# cpuboard.net
KiCad netlist of a schematic drawn in EAGLE
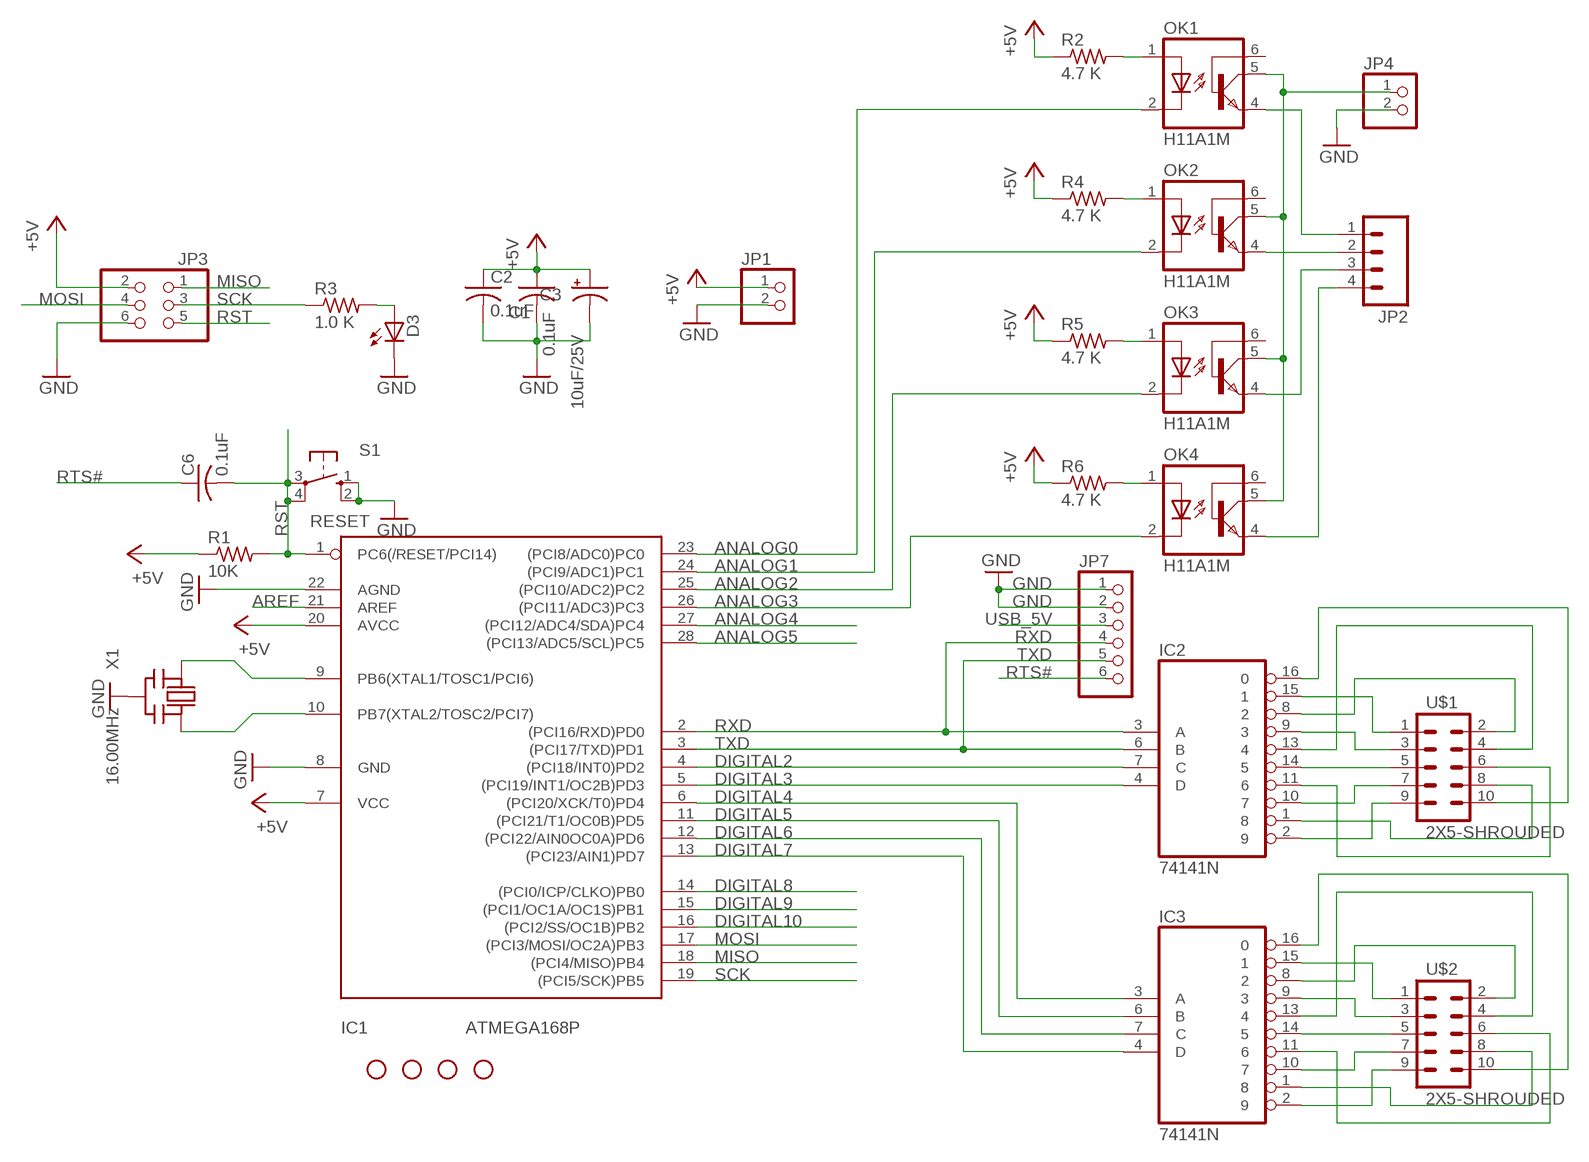
[diagram p0: schematic, sheet 1]

(export (version "E")
  (design (tool "Eeschema 10.0.6"))
  (components
    (comp (ref "C1")
      (value "0.1uF")
      (footprint "eagle-import:C025-025X050")
      (libsource (lib "eagle-import") (part "C-US025-025X050"))
    )
    (comp (ref "C2")
      (value "0.1uF")
      (footprint "eagle-import:C025-025X050")
      (libsource (lib "eagle-import") (part "C-US025-025X050"))
    )
    (comp (ref "C3")
      (value "10uF/25V")
      (footprint "eagle-import:E2,5-6")
      (libsource (lib "eagle-import") (part "CPOL-USE2.5-6"))
    )
    (comp (ref "C6")
      (value "0.1uF")
      (footprint "eagle-import:C025-025X050")
      (libsource (lib "eagle-import") (part "C-US025-025X050"))
    )
    (comp (ref "D3")
      (value "Green")
      (footprint "eagle-import:LED3MM")
      (libsource (lib "eagle-import") (part "LED3MM"))
    )
    (comp (ref "IC1")
      (value "ATMEGA168P")
      (footprint "eagle-import:DIL28_3")
      (libsource (lib "eagle-import") (part "ATMEGA168PROUND"))
    )
    (comp (ref "IC2")
      (value "74141N")
      (footprint "eagle-import:DIL16")
      (libsource (lib "eagle-import") (part "74141N"))
    )
    (comp (ref "IC3")
      (value "74141N")
      (footprint "eagle-import:DIL16")
      (libsource (lib "eagle-import") (part "74141N"))
    )
    (comp (ref "JP1")
      (value "PINHD-1X2CB")
      (footprint "eagle-import:1X02-CB")
      (libsource (lib "eagle-import") (part "PINHD-1X2CB"))
    )
    (comp (ref "JP2")
      (value "M04PTH")
      (footprint "eagle-import:1X04")
      (libsource (lib "eagle-import") (part "M04PTH"))
    )
    (comp (ref "JP3")
      (value "PINHD-2X3")
      (footprint "eagle-import:2X03")
      (libsource (lib "eagle-import") (part "PINHD-2X3"))
    )
    (comp (ref "JP4")
      (value "PINHD-1X2CB")
      (footprint "eagle-import:1X02-CB")
      (libsource (lib "eagle-import") (part "PINHD-1X2CB"))
    )
    (comp (ref "JP7")
      (value "PINHD-1X6CLEAN")
      (footprint "eagle-import:1X06-CLEAN")
      (libsource (lib "eagle-import") (part "PINHD-1X6CLEAN"))
    )
    (comp (ref "OK1")
      (value "H11A1M")
      (footprint "eagle-import:DIL06")
      (fields (field (name "MPN") "H11A1-M"))
      (libsource (lib "eagle-import") (part "H11A?M1"))
    )
    (comp (ref "OK2")
      (value "H11A1M")
      (footprint "eagle-import:DIL06")
      (fields (field (name "MPN") "H11A1-M"))
      (libsource (lib "eagle-import") (part "H11A?M1"))
    )
    (comp (ref "OK3")
      (value "H11A1M")
      (footprint "eagle-import:DIL06")
      (fields (field (name "MPN") "H11A1-M"))
      (libsource (lib "eagle-import") (part "H11A?M1"))
    )
    (comp (ref "OK4")
      (value "H11A1M")
      (footprint "eagle-import:DIL06")
      (fields (field (name "MPN") "H11A1-M"))
      (libsource (lib "eagle-import") (part "H11A?M1"))
    )
    (comp (ref "R1")
      (value "10K")
      (footprint "eagle-import:0207_5V")
      (libsource (lib "eagle-import") (part "rcl-ez_R-US_0207/5V"))
    )
    (comp (ref "R2")
      (value "4.7 K")
      (footprint "eagle-import:0207_5V")
      (libsource (lib "eagle-import") (part "R-US_0207/5V"))
    )
    (comp (ref "R3")
      (value "1.0 K")
      (footprint "eagle-import:0207_5V")
      (libsource (lib "eagle-import") (part "R-US_0207/5V"))
    )
    (comp (ref "R4")
      (value "4.7 K")
      (footprint "eagle-import:0207_5V")
      (libsource (lib "eagle-import") (part "R-US_0207/5V"))
    )
    (comp (ref "R5")
      (value "4.7 K")
      (footprint "eagle-import:0207_5V")
      (libsource (lib "eagle-import") (part "R-US_0207/5V"))
    )
    (comp (ref "R6")
      (value "4.7 K")
      (footprint "eagle-import:0207_5V")
      (libsource (lib "eagle-import") (part "R-US_0207/5V"))
    )
    (comp (ref "S1")
      (value "RESET")
      (footprint "eagle-import:B3F-10XX")
      (libsource (lib "eagle-import") (part "10-XX"))
    )
    (comp (ref "STANDOFF1")
      (value "STAND-OFF")
      (footprint "eagle-import:STAND-OFF")
      (libsource (lib "eagle-import") (part "STAND-OFF"))
    )
    (comp (ref "STANDOFF2")
      (value "STAND-OFF")
      (footprint "eagle-import:STAND-OFF")
      (libsource (lib "eagle-import") (part "STAND-OFF"))
    )
    (comp (ref "STANDOFF3")
      (value "STAND-OFF")
      (footprint "eagle-import:STAND-OFF")
      (libsource (lib "eagle-import") (part "STAND-OFF"))
    )
    (comp (ref "STANDOFF4")
      (value "STAND-OFF")
      (footprint "eagle-import:STAND-OFF")
      (libsource (lib "eagle-import") (part "STAND-OFF"))
    )
    (comp (ref "U$1")
      (value "2X5-SHROUDED")
      (footprint "eagle-import:2X5-SHROUDED")
      (libsource (lib "eagle-import") (part "2X5-SHROUDED"))
    )
    (comp (ref "U$2")
      (value "2X5-SHROUDED")
      (footprint "eagle-import:2X5-SHROUDED")
      (libsource (lib "eagle-import") (part "2X5-SHROUDED"))
    )
    (comp (ref "X1")
      (value "16.00MHz")
      (footprint "eagle-import:CERM_OSC")
      (libsource (lib "eagle-import") (part "CERMOSCILL"))
    )
  )
  (nets
    (net (code "1") (name "+5V") (class "Default")
      (node (ref "C1") (pin "1") (pinfunction "1_1") (pintype "passive"))
      (node (ref "C2") (pin "1") (pinfunction "1_1") (pintype "passive"))
      (node (ref "C3") (pin "+") (pinfunction "+_+") (pintype "passive"))
      (node (ref "IC1") (pin "20") (pinfunction "AVCC_20") (pintype "bidirectional"))
      (node (ref "IC1") (pin "7") (pinfunction "VCC_7") (pintype "bidirectional"))
      (node (ref "JP1") (pin "1") (pinfunction "1_1") (pintype "passive"))
      (node (ref "JP3") (pin "2") (pinfunction "2_2") (pintype "passive"))
      (node (ref "R1") (pin "1") (pinfunction "1_1") (pintype "passive"))
      (node (ref "R2") (pin "1") (pinfunction "1_1") (pintype "passive"))
      (node (ref "R4") (pin "1") (pinfunction "1_1") (pintype "passive"))
      (node (ref "R5") (pin "1") (pinfunction "1_1") (pintype "passive"))
      (node (ref "R6") (pin "1") (pinfunction "1_1") (pintype "passive"))
    )
    (net (code "2") (name "/ANALOG0") (class "Default")
      (node (ref "IC1") (pin "23") (pinfunction "(PCI8/ADC0)PC0_23") (pintype "bidirectional"))
      (node (ref "OK1") (pin "2") (pinfunction "C_2") (pintype "passive"))
    )
    (net (code "3") (name "/ANALOG1") (class "Default")
      (node (ref "IC1") (pin "24") (pinfunction "(PCI9/ADC1)PC1_24") (pintype "bidirectional"))
      (node (ref "OK2") (pin "2") (pinfunction "C_2") (pintype "passive"))
    )
    (net (code "4") (name "/ANALOG2") (class "Default")
      (node (ref "IC1") (pin "25") (pinfunction "(PCI10/ADC2)PC2_25") (pintype "bidirectional"))
      (node (ref "OK3") (pin "2") (pinfunction "C_2") (pintype "passive"))
    )
    (net (code "5") (name "/ANALOG3") (class "Default")
      (node (ref "IC1") (pin "26") (pinfunction "(PCI11/ADC3)PC3_26") (pintype "bidirectional"))
      (node (ref "OK4") (pin "2") (pinfunction "C_2") (pintype "passive"))
    )
    (net (code "6") (name "/ANALOG4") (class "Default")
      (node (ref "IC1") (pin "27") (pinfunction "(PCI12/ADC4/SDA)PC4_27") (pintype "bidirectional"))
    )
    (net (code "7") (name "/ANALOG5") (class "Default")
      (node (ref "IC1") (pin "28") (pinfunction "(PCI13/ADC5/SCL)PC5_28") (pintype "bidirectional"))
    )
    (net (code "8") (name "/AREF") (class "Default")
      (node (ref "IC1") (pin "21") (pinfunction "AREF_21") (pintype "bidirectional"))
    )
    (net (code "9") (name "/DIGITAL2") (class "Default")
      (node (ref "IC1") (pin "4") (pinfunction "(PCI18/INT0)PD2_4") (pintype "bidirectional"))
      (node (ref "IC2") (pin "7") (pinfunction "C_7") (pintype "input"))
    )
    (net (code "10") (name "/DIGITAL3") (class "Default")
      (node (ref "IC1") (pin "5") (pinfunction "(PCI19/INT1/OC2B)PD3_5") (pintype "bidirectional"))
      (node (ref "IC2") (pin "4") (pinfunction "D_4") (pintype "input"))
    )
    (net (code "11") (name "/DIGITAL4") (class "Default")
      (node (ref "IC1") (pin "6") (pinfunction "(PCI20/XCK/T0)PD4_6") (pintype "bidirectional"))
      (node (ref "IC3") (pin "3") (pinfunction "A_3") (pintype "input"))
    )
    (net (code "12") (name "/DIGITAL5") (class "Default")
      (node (ref "IC1") (pin "11") (pinfunction "(PCI21/T1/OC0B)PD5_11") (pintype "bidirectional"))
      (node (ref "IC3") (pin "6") (pinfunction "B_6") (pintype "input"))
    )
    (net (code "13") (name "/DIGITAL6") (class "Default")
      (node (ref "IC1") (pin "12") (pinfunction "(PCI22/AIN0OC0A)PD6_12") (pintype "bidirectional"))
      (node (ref "IC3") (pin "7") (pinfunction "C_7") (pintype "input"))
    )
    (net (code "14") (name "/DIGITAL7") (class "Default")
      (node (ref "IC1") (pin "13") (pinfunction "(PCI23/AIN1)PD7_13") (pintype "bidirectional"))
      (node (ref "IC3") (pin "4") (pinfunction "D_4") (pintype "input"))
    )
    (net (code "15") (name "/DIGITAL8") (class "Default")
      (node (ref "IC1") (pin "14") (pinfunction "(PCI0/ICP/CLKO)PB0_14") (pintype "bidirectional"))
    )
    (net (code "16") (name "/DIGITAL9") (class "Default")
      (node (ref "IC1") (pin "15") (pinfunction "(PCI1/OC1A/OC1S)PB1_15") (pintype "bidirectional"))
    )
    (net (code "17") (name "/DIGITAL10") (class "Default")
      (node (ref "IC1") (pin "16") (pinfunction "(PCI2/SS/OC1B)PB2_16") (pintype "bidirectional"))
    )
    (net (code "18") (name "/MISO") (class "Default")
      (node (ref "IC1") (pin "18") (pinfunction "(PCI4/MISO)PB4_18") (pintype "bidirectional"))
      (node (ref "JP3") (pin "1") (pinfunction "1_1") (pintype "passive"))
    )
    (net (code "19") (name "/MOSI") (class "Default")
      (node (ref "IC1") (pin "17") (pinfunction "(PCI3/MOSI/OC2A)PB3_17") (pintype "bidirectional"))
      (node (ref "JP3") (pin "4") (pinfunction "4_4") (pintype "passive"))
    )
    (net (code "20") (name "/RST") (class "Default")
      (node (ref "C6") (pin "2") (pinfunction "2_2") (pintype "passive"))
      (node (ref "IC1") (pin "1") (pinfunction "PC6(/RESET/PCI14)_1") (pintype "bidirectional"))
      (node (ref "JP3") (pin "5") (pinfunction "5_5") (pintype "passive"))
      (node (ref "R1") (pin "2") (pinfunction "2_2") (pintype "passive"))
      (node (ref "S1") (pin "3") (pinfunction "P_3") (pintype "passive"))
      (node (ref "S1") (pin "4") (pinfunction "P1_4") (pintype "passive"))
    )
    (net (code "21") (name "/RTS#") (class "Default")
      (node (ref "C6") (pin "1") (pinfunction "1_1") (pintype "passive"))
      (node (ref "JP7") (pin "6") (pinfunction "6_6") (pintype "passive"))
    )
    (net (code "22") (name "/RXD") (class "Default")
      (node (ref "IC1") (pin "2") (pinfunction "(PCI16/RXD)PD0_2") (pintype "bidirectional"))
      (node (ref "IC2") (pin "3") (pinfunction "A_3") (pintype "input"))
      (node (ref "JP7") (pin "4") (pinfunction "4_4") (pintype "passive"))
    )
    (net (code "23") (name "/SCK") (class "Default")
      (node (ref "IC1") (pin "19") (pinfunction "(PCI5/SCK)PB5_19") (pintype "bidirectional"))
      (node (ref "JP3") (pin "3") (pinfunction "3_3") (pintype "passive"))
      (node (ref "R3") (pin "1") (pinfunction "1_1") (pintype "passive"))
    )
    (net (code "24") (name "/TXD") (class "Default")
      (node (ref "IC1") (pin "3") (pinfunction "(PCI17/TXD)PD1_3") (pintype "bidirectional"))
      (node (ref "IC2") (pin "6") (pinfunction "B_6") (pintype "input"))
      (node (ref "JP7") (pin "5") (pinfunction "5_5") (pintype "passive"))
    )
    (net (code "25") (name "/USB_5V") (class "Default")
      (node (ref "JP7") (pin "3") (pinfunction "3_3") (pintype "passive"))
    )
    (net (code "26") (name "GND") (class "Default")
      (node (ref "C1") (pin "2") (pinfunction "2_2") (pintype "passive"))
      (node (ref "C2") (pin "2") (pinfunction "2_2") (pintype "passive"))
      (node (ref "C3") (pin "-") (pinfunction "-_-") (pintype "passive"))
      (node (ref "D3") (pin "K") (pinfunction "C_K") (pintype "passive"))
      (node (ref "IC1") (pin "22") (pinfunction "AGND_22") (pintype "bidirectional"))
      (node (ref "IC1") (pin "8") (pinfunction "GND_8") (pintype "bidirectional"))
      (node (ref "JP1") (pin "2") (pinfunction "2_2") (pintype "passive"))
      (node (ref "JP3") (pin "6") (pinfunction "6_6") (pintype "passive"))
      (node (ref "JP4") (pin "2") (pinfunction "2_2") (pintype "passive"))
      (node (ref "JP7") (pin "1") (pinfunction "1_1") (pintype "passive"))
      (node (ref "JP7") (pin "2") (pinfunction "2_2") (pintype "passive"))
      (node (ref "S1") (pin "1") (pinfunction "S_1") (pintype "passive"))
      (node (ref "S1") (pin "2") (pinfunction "S1_2") (pintype "passive"))
      (node (ref "X1") (pin "P$2") (pinfunction "GND_P$2") (pintype "bidirectional"))
    )
    (net (code "27") (name "Net-(D3-PadA)") (class "Default")
      (node (ref "D3") (pin "A") (pinfunction "A_A") (pintype "passive"))
      (node (ref "R3") (pin "2") (pinfunction "2_2") (pintype "passive"))
    )
    (net (code "28") (name "Net-(IC1-PB6(XTAL1{slash}TOSC1{slash}PCI6))") (class "Default")
      (node (ref "IC1") (pin "9") (pinfunction "PB6(XTAL1/TOSC1/PCI6)_9") (pintype "bidirectional"))
      (node (ref "X1") (pin "P$1") (pinfunction "IN_P$1") (pintype "bidirectional"))
    )
    (net (code "29") (name "Net-(IC1-PB7(XTAL2{slash}TOSC2{slash}PCI7))") (class "Default")
      (node (ref "IC1") (pin "10") (pinfunction "PB7(XTAL2/TOSC2/PCI7)_10") (pintype "bidirectional"))
      (node (ref "X1") (pin "P$3") (pinfunction "OUT_P$3") (pintype "bidirectional"))
    )
    (net (code "30") (name "Net-(IC2A-0)") (class "Default")
      (node (ref "IC2") (pin "16") (pinfunction "0_16") (pintype "open_collector"))
      (node (ref "U$1") (pin "10") (pinfunction "10_10") (pintype "passive"))
    )
    (net (code "31") (name "Net-(IC2A-1)") (class "Default")
      (node (ref "IC2") (pin "15") (pinfunction "1_15") (pintype "open_collector"))
      (node (ref "U$1") (pin "1") (pinfunction "1_1") (pintype "passive"))
    )
    (net (code "32") (name "Net-(IC2A-2)") (class "Default")
      (node (ref "IC2") (pin "8") (pinfunction "2_8") (pintype "open_collector"))
      (node (ref "U$1") (pin "2") (pinfunction "2_2") (pintype "passive"))
    )
    (net (code "33") (name "Net-(IC2A-3)") (class "Default")
      (node (ref "IC2") (pin "9") (pinfunction "3_9") (pintype "open_collector"))
      (node (ref "U$1") (pin "3") (pinfunction "3_3") (pintype "passive"))
    )
    (net (code "34") (name "Net-(IC2A-4)") (class "Default")
      (node (ref "IC2") (pin "13") (pinfunction "4_13") (pintype "open_collector"))
      (node (ref "U$1") (pin "4") (pinfunction "4_4") (pintype "passive"))
    )
    (net (code "35") (name "Net-(IC2A-5)") (class "Default")
      (node (ref "IC2") (pin "14") (pinfunction "5_14") (pintype "open_collector"))
      (node (ref "U$1") (pin "5") (pinfunction "5_5") (pintype "passive"))
    )
    (net (code "36") (name "Net-(IC2A-6)") (class "Default")
      (node (ref "IC2") (pin "11") (pinfunction "6_11") (pintype "open_collector"))
      (node (ref "U$1") (pin "6") (pinfunction "6_6") (pintype "passive"))
    )
    (net (code "37") (name "Net-(IC2A-7)") (class "Default")
      (node (ref "IC2") (pin "10") (pinfunction "7_10") (pintype "open_collector"))
      (node (ref "U$1") (pin "7") (pinfunction "7_7") (pintype "passive"))
    )
    (net (code "38") (name "Net-(IC2A-8)") (class "Default")
      (node (ref "IC2") (pin "1") (pinfunction "8_1") (pintype "open_collector"))
      (node (ref "U$1") (pin "8") (pinfunction "8_8") (pintype "passive"))
    )
    (net (code "39") (name "Net-(IC2A-9)") (class "Default")
      (node (ref "IC2") (pin "2") (pinfunction "9_2") (pintype "open_collector"))
      (node (ref "U$1") (pin "9") (pinfunction "9_9") (pintype "passive"))
    )
    (net (code "40") (name "Net-(IC3A-0)") (class "Default")
      (node (ref "IC3") (pin "16") (pinfunction "0_16") (pintype "open_collector"))
      (node (ref "U$2") (pin "10") (pinfunction "10_10") (pintype "passive"))
    )
    (net (code "41") (name "Net-(IC3A-1)") (class "Default")
      (node (ref "IC3") (pin "15") (pinfunction "1_15") (pintype "open_collector"))
      (node (ref "U$2") (pin "1") (pinfunction "1_1") (pintype "passive"))
    )
    (net (code "42") (name "Net-(IC3A-2)") (class "Default")
      (node (ref "IC3") (pin "8") (pinfunction "2_8") (pintype "open_collector"))
      (node (ref "U$2") (pin "2") (pinfunction "2_2") (pintype "passive"))
    )
    (net (code "43") (name "Net-(IC3A-3)") (class "Default")
      (node (ref "IC3") (pin "9") (pinfunction "3_9") (pintype "open_collector"))
      (node (ref "U$2") (pin "3") (pinfunction "3_3") (pintype "passive"))
    )
    (net (code "44") (name "Net-(IC3A-4)") (class "Default")
      (node (ref "IC3") (pin "13") (pinfunction "4_13") (pintype "open_collector"))
      (node (ref "U$2") (pin "4") (pinfunction "4_4") (pintype "passive"))
    )
    (net (code "45") (name "Net-(IC3A-5)") (class "Default")
      (node (ref "IC3") (pin "14") (pinfunction "5_14") (pintype "open_collector"))
      (node (ref "U$2") (pin "5") (pinfunction "5_5") (pintype "passive"))
    )
    (net (code "46") (name "Net-(IC3A-6)") (class "Default")
      (node (ref "IC3") (pin "11") (pinfunction "6_11") (pintype "open_collector"))
      (node (ref "U$2") (pin "6") (pinfunction "6_6") (pintype "passive"))
    )
    (net (code "47") (name "Net-(IC3A-7)") (class "Default")
      (node (ref "IC3") (pin "10") (pinfunction "7_10") (pintype "open_collector"))
      (node (ref "U$2") (pin "7") (pinfunction "7_7") (pintype "passive"))
    )
    (net (code "48") (name "Net-(IC3A-8)") (class "Default")
      (node (ref "IC3") (pin "1") (pinfunction "8_1") (pintype "open_collector"))
      (node (ref "U$2") (pin "8") (pinfunction "8_8") (pintype "passive"))
    )
    (net (code "49") (name "Net-(IC3A-9)") (class "Default")
      (node (ref "IC3") (pin "2") (pinfunction "9_2") (pintype "open_collector"))
      (node (ref "U$2") (pin "9") (pinfunction "9_9") (pintype "passive"))
    )
    (net (code "50") (name "Net-(OK1-A)") (class "Default")
      (node (ref "OK1") (pin "1") (pinfunction "A_1") (pintype "passive"))
      (node (ref "R2") (pin "2") (pinfunction "2_2") (pintype "passive"))
    )
    (net (code "51") (name "Net-(OK1-COL)") (class "Default")
      (node (ref "JP4") (pin "1") (pinfunction "1_1") (pintype "passive"))
      (node (ref "OK1") (pin "5") (pinfunction "COL_5") (pintype "passive"))
      (node (ref "OK2") (pin "5") (pinfunction "COL_5") (pintype "passive"))
      (node (ref "OK3") (pin "5") (pinfunction "COL_5") (pintype "passive"))
      (node (ref "OK4") (pin "5") (pinfunction "COL_5") (pintype "passive"))
    )
    (net (code "52") (name "Net-(OK1-EMI)") (class "Default")
      (node (ref "JP2") (pin "1") (pinfunction "1_1") (pintype "passive"))
      (node (ref "OK1") (pin "4") (pinfunction "EMI_4") (pintype "passive"))
    )
    (net (code "53") (name "Net-(OK2-A)") (class "Default")
      (node (ref "OK2") (pin "1") (pinfunction "A_1") (pintype "passive"))
      (node (ref "R4") (pin "2") (pinfunction "2_2") (pintype "passive"))
    )
    (net (code "54") (name "Net-(OK2-EMI)") (class "Default")
      (node (ref "JP2") (pin "2") (pinfunction "2_2") (pintype "passive"))
      (node (ref "OK2") (pin "4") (pinfunction "EMI_4") (pintype "passive"))
    )
    (net (code "55") (name "Net-(OK3-A)") (class "Default")
      (node (ref "OK3") (pin "1") (pinfunction "A_1") (pintype "passive"))
      (node (ref "R5") (pin "2") (pinfunction "2_2") (pintype "passive"))
    )
    (net (code "56") (name "Net-(OK3-EMI)") (class "Default")
      (node (ref "JP2") (pin "3") (pinfunction "3_3") (pintype "passive"))
      (node (ref "OK3") (pin "4") (pinfunction "EMI_4") (pintype "passive"))
    )
    (net (code "57") (name "Net-(OK4-A)") (class "Default")
      (node (ref "OK4") (pin "1") (pinfunction "A_1") (pintype "passive"))
      (node (ref "R6") (pin "2") (pinfunction "2_2") (pintype "passive"))
    )
    (net (code "58") (name "Net-(OK4-EMI)") (class "Default")
      (node (ref "JP2") (pin "4") (pinfunction "4_4") (pintype "passive"))
      (node (ref "OK4") (pin "4") (pinfunction "EMI_4") (pintype "passive"))
    )
    (net (code "59") (name "unconnected-(OK1-BAS-Pad6)") (class "Default")
      (node (ref "OK1") (pin "6") (pinfunction "BAS_6") (pintype "passive"))
    )
    (net (code "60") (name "unconnected-(OK2-BAS-Pad6)") (class "Default")
      (node (ref "OK2") (pin "6") (pinfunction "BAS_6") (pintype "passive"))
    )
    (net (code "61") (name "unconnected-(OK3-BAS-Pad6)") (class "Default")
      (node (ref "OK3") (pin "6") (pinfunction "BAS_6") (pintype "passive"))
    )
    (net (code "62") (name "unconnected-(OK4-BAS-Pad6)") (class "Default")
      (node (ref "OK4") (pin "6") (pinfunction "BAS_6") (pintype "passive"))
    )
  )
)
